# G1000_Nav_Switch.net
KiCad netlist of a schematic drawn in EasyEDA
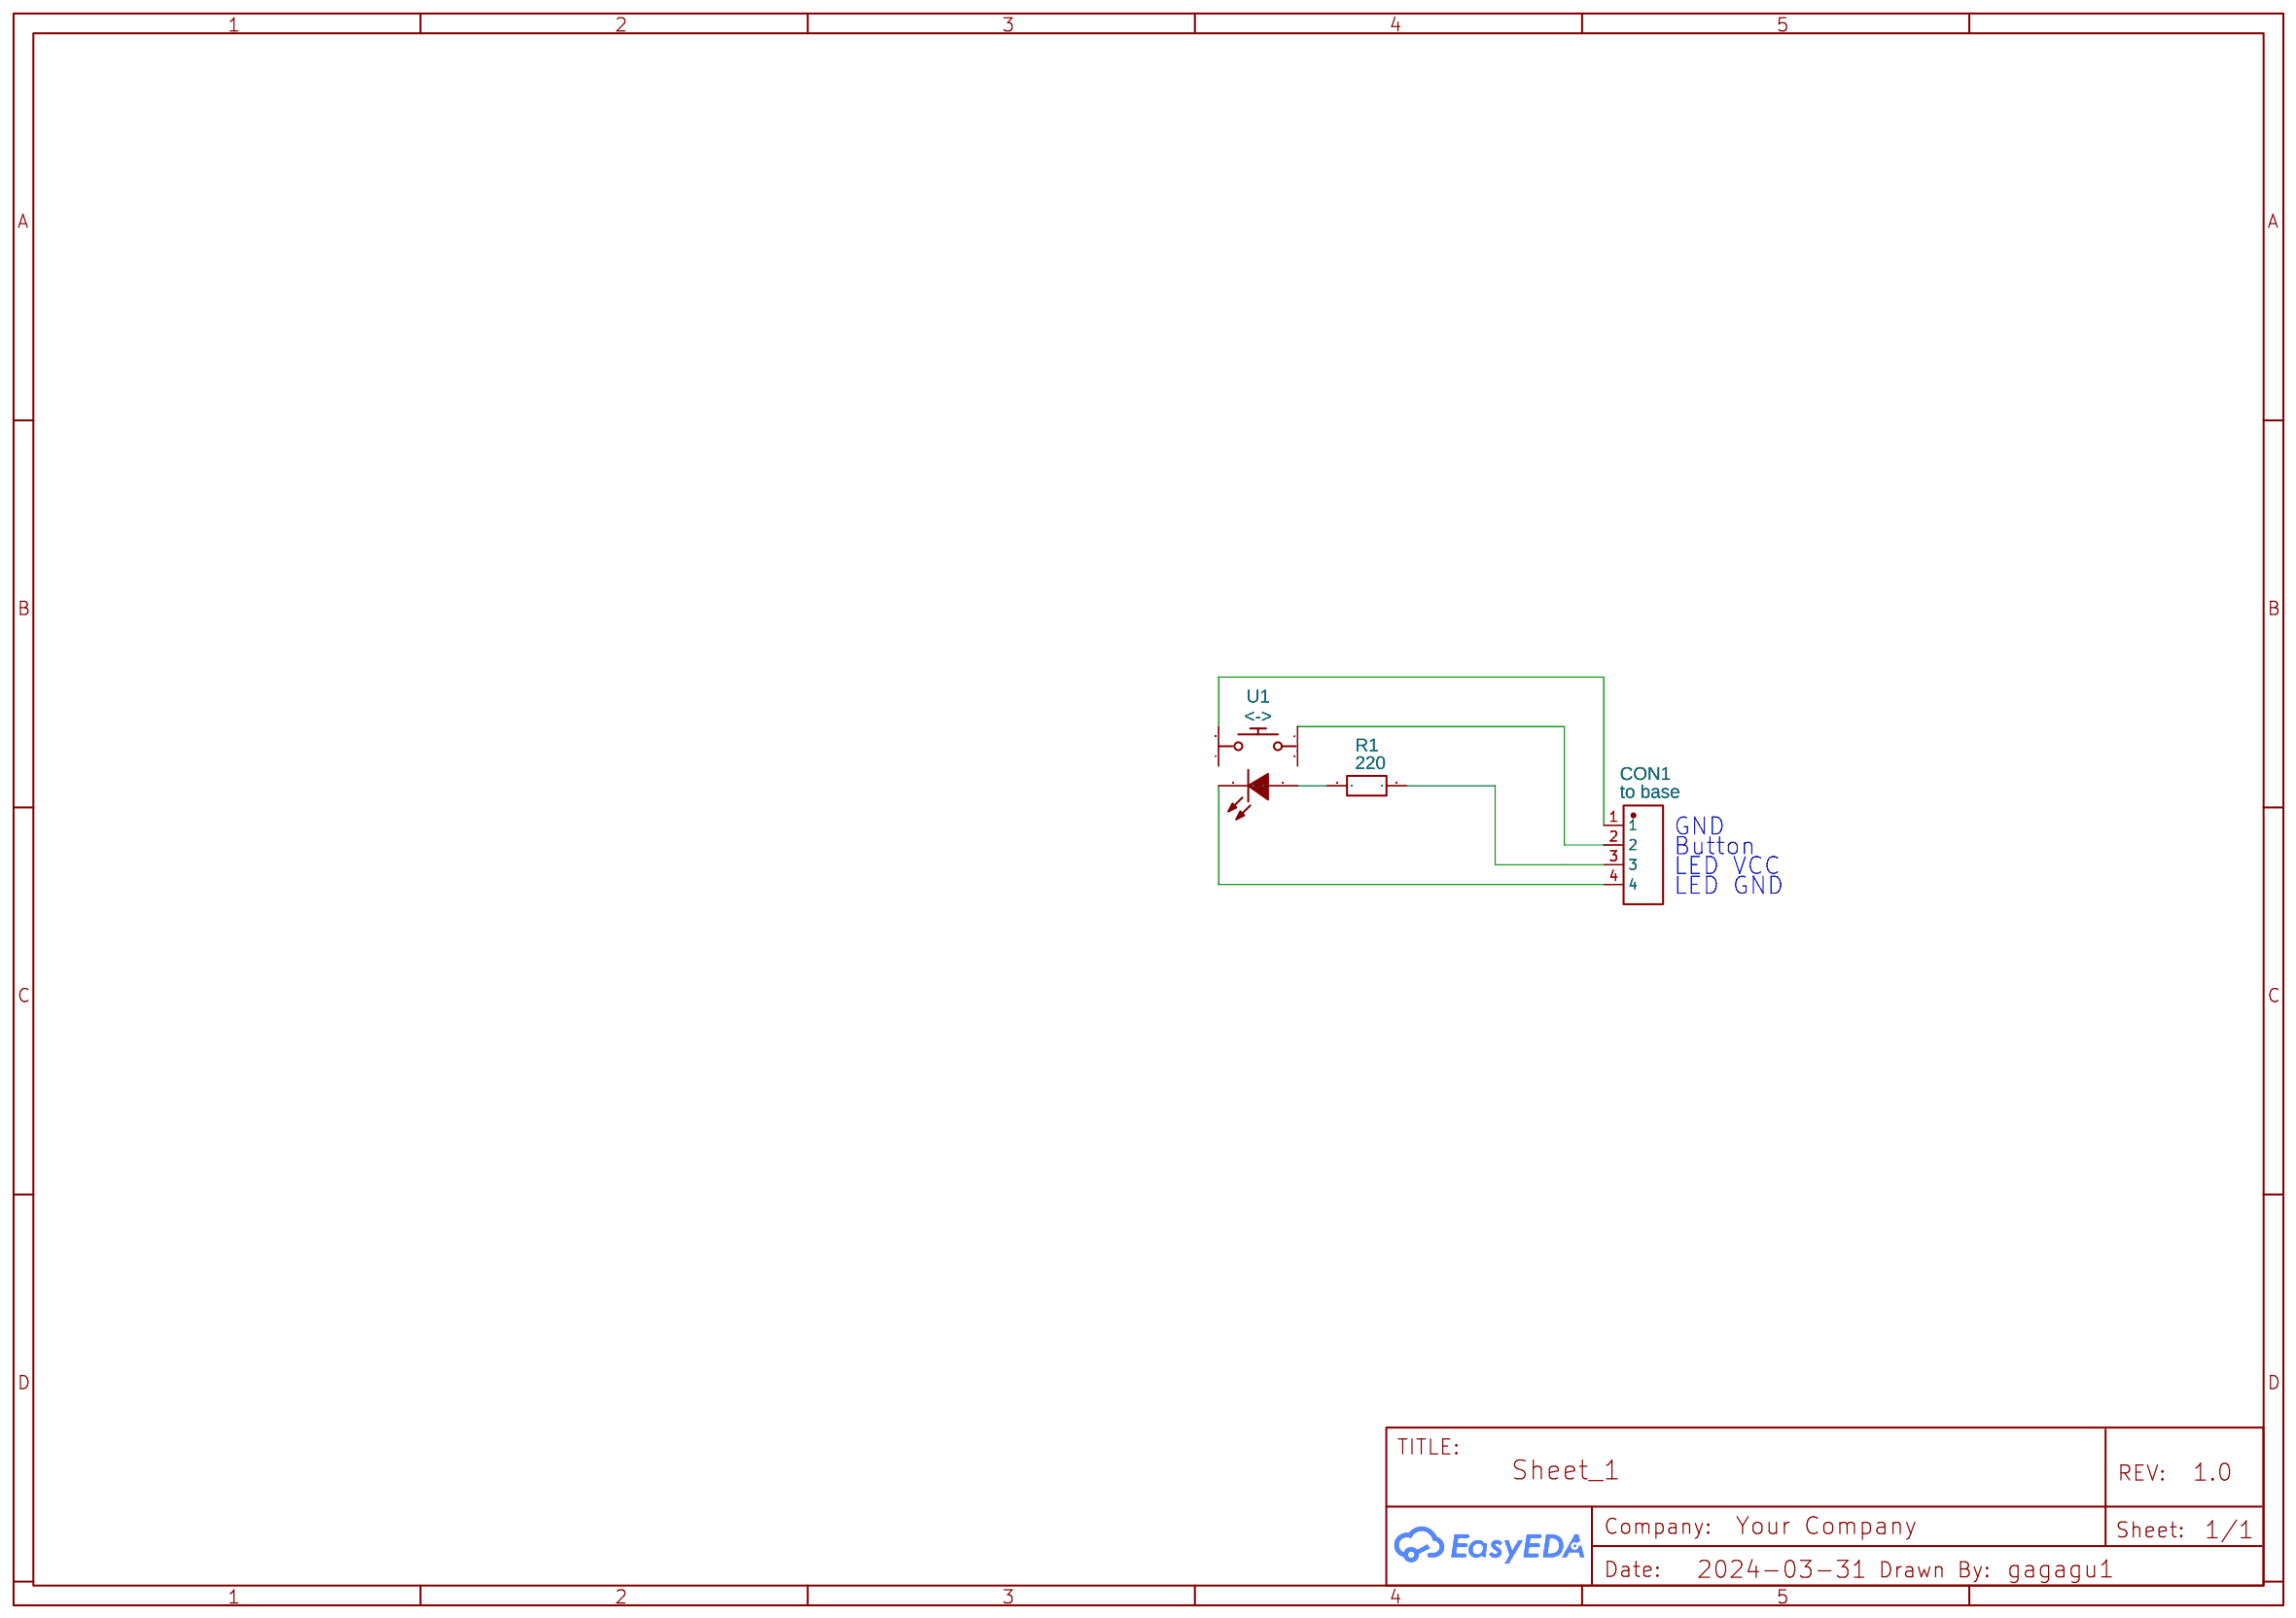
[diagram p0: schematic sheet]

(export (version "E")
  (design (tool "Eeschema 10.0.6"))
  (components
    (comp (ref "CON1")
      (value "to base")
      (fields
        (field (name "Manufacturer Part") "A2541HWV-4P")
        (field (name "Manufacturer") "Changjiang Connectors")
      )
      (libsource (lib "") (part "1X4PIN"))
    )
    (comp (ref "R1") (value "220") (libsource (lib "") (part "R_AXIAL-0.4_EU")))
    (comp (ref "U1") (value "<->") (libsource (lib "") (part "6X6_LED+PUSHBUTTON V2")))
  )
  (nets
    (net (code "1") (name "Net-(CON1-Pad1)") (class "Default")
      (node (ref "CON1") (pin "1") (pinfunction "1_1") (pintype "unspecified"))
      (node (ref "U1") (pin "3") (pinfunction "3_3") (pintype "unspecified"))
    )
    (net (code "2") (name "Net-(CON1-Pad2)") (class "Default")
      (node (ref "CON1") (pin "2") (pinfunction "2_2") (pintype "unspecified"))
      (node (ref "U1") (pin "1") (pinfunction "1_1") (pintype "unspecified"))
    )
    (net (code "3") (name "Net-(CON1-Pad3)") (class "Default")
      (node (ref "CON1") (pin "3") (pinfunction "3_3") (pintype "unspecified"))
      (node (ref "R1") (pin "1") (pinfunction "1_1") (pintype "unspecified"))
    )
    (net (code "4") (name "Net-(CON1-Pad4)") (class "Default")
      (node (ref "CON1") (pin "4") (pinfunction "4_4") (pintype "unspecified"))
      (node (ref "U1") (pin "C") (pinfunction "C_C") (pintype "unspecified"))
    )
    (net (code "5") (name "Net-(R1-Pad2)") (class "Default")
      (node (ref "R1") (pin "2") (pinfunction "2_2") (pintype "unspecified"))
      (node (ref "U1") (pin "A") (pinfunction "A_A") (pintype "unspecified"))
    )
    (net (code "6") (name "unconnected-(U1-Pad2)") (class "Default")
      (node (ref "U1") (pin "2") (pinfunction "2_2") (pintype "unspecified"))
    )
    (net (code "7") (name "unconnected-(U1-Pad4)") (class "Default")
      (node (ref "U1") (pin "4") (pinfunction "4_4") (pintype "unspecified"))
    )
  )
)
